# BT_AQ_DOL_R3.net
KiCad netlist of a schematic drawn in EAGLE
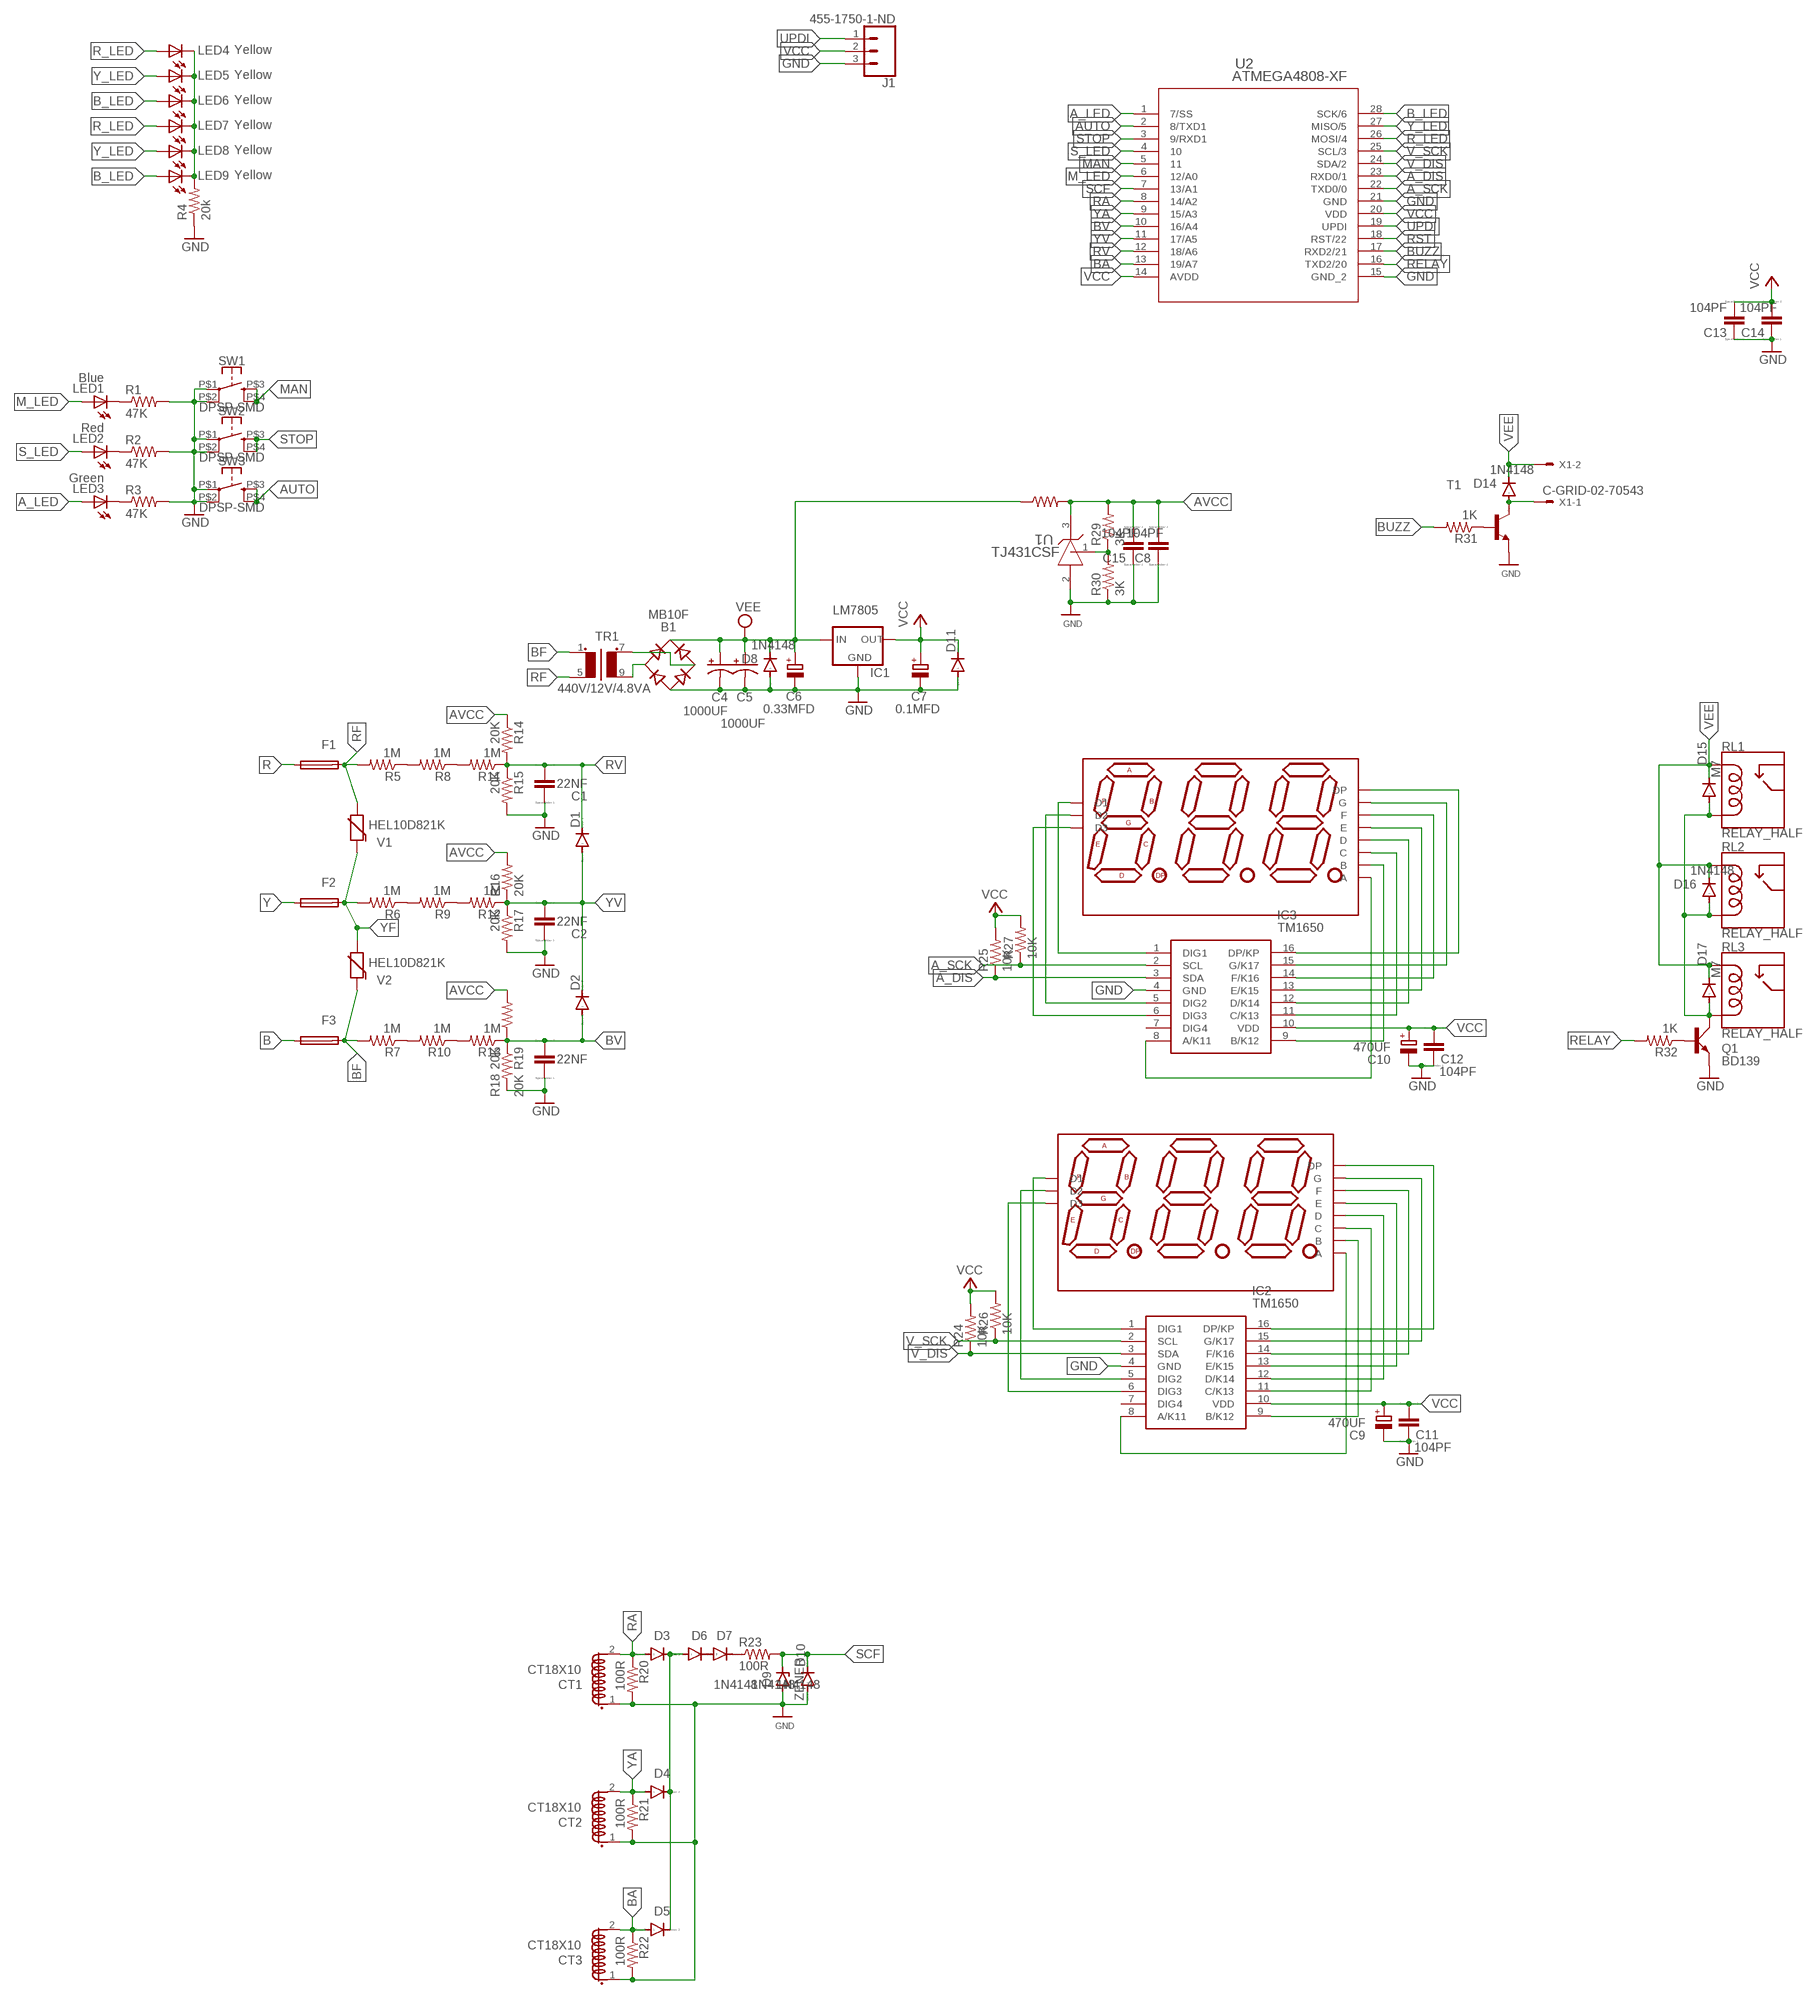
[diagram p0: schematic, sheet 1]

(export (version "E")
  (design (tool "Eeschema 10.0.6"))
  (components
    (comp (ref "B1")
      (value "MB10F")
      (footprint "eagle-import:SOIC-4")
      (libsource (lib "eagle-import") (part "MBS8"))
    )
    (comp (ref "C1")
      (value "22NF")
      (footprint "eagle-import:C1206")
      (libsource (lib "eagle-import") (part "CC1206"))
    )
    (comp (ref "C2")
      (value "22NF")
      (footprint "eagle-import:C1206")
      (libsource (lib "eagle-import") (part "CC1206"))
    )
    (comp (ref "C3")
      (value "22NF")
      (footprint "eagle-import:C1206")
      (libsource (lib "eagle-import") (part "CC1206"))
    )
    (comp (ref "C4")
      (value "1000UF")
      (footprint "eagle-import:E3,5-10")
      (libsource (lib "eagle-import") (part "CPOL-USE3.5-10"))
    )
    (comp (ref "C5")
      (value "1000UF")
      (footprint "eagle-import:E3,5-10")
      (libsource (lib "eagle-import") (part "CPOL-USE3.5-10"))
    )
    (comp (ref "C6")
      (value "0.33MFD")
      (footprint "eagle-import:E2,5-5")
      (libsource (lib "eagle-import") (part "CPOL-EUE2.5-5"))
    )
    (comp (ref "C7")
      (value "0.1MFD")
      (footprint "eagle-import:E2,5-5")
      (libsource (lib "eagle-import") (part "CPOL-EUE2.5-5"))
    )
    (comp (ref "C8")
      (value "104PF")
      (footprint "eagle-import:C1206")
      (libsource (lib "eagle-import") (part "CC1206"))
    )
    (comp (ref "C9")
      (value "470UF")
      (footprint "eagle-import:E3,5-8")
      (libsource (lib "eagle-import") (part "CPOL-EUE3.5-8"))
    )
    (comp (ref "C10")
      (value "470UF")
      (footprint "eagle-import:E3,5-8")
      (libsource (lib "eagle-import") (part "CPOL-EUE3.5-8"))
    )
    (comp (ref "C11")
      (value "104PF")
      (footprint "eagle-import:C1206")
      (libsource (lib "eagle-import") (part "CC1206"))
    )
    (comp (ref "C12")
      (value "104PF")
      (footprint "eagle-import:C1206")
      (libsource (lib "eagle-import") (part "CC1206"))
    )
    (comp (ref "C13")
      (value "104PF")
      (footprint "eagle-import:C1206")
      (libsource (lib "eagle-import") (part "CC1206"))
    )
    (comp (ref "C14")
      (value "104PF")
      (footprint "eagle-import:C1206")
      (libsource (lib "eagle-import") (part "CC1206"))
    )
    (comp (ref "C15")
      (value "104PF")
      (footprint "eagle-import:C1206")
      (libsource (lib "eagle-import") (part "CC1206"))
    )
    (comp (ref "CT1")
      (value "CT18X10")
      (footprint "eagle-import:ZMCT103C")
      (libsource (lib "eagle-import") (part "CT18X10"))
    )
    (comp (ref "CT2")
      (value "CT18X10")
      (footprint "eagle-import:ZMCT103C")
      (libsource (lib "eagle-import") (part "CT18X10"))
    )
    (comp (ref "CT3")
      (value "CT18X10")
      (footprint "eagle-import:ZMCT103C")
      (libsource (lib "eagle-import") (part "CT18X10"))
    )
    (comp (ref "D1")
      (value "DIODE-DO214AA")
      (footprint "eagle-import:DO214AA")
      (libsource (lib "eagle-import") (part "DIODE-DO214AA"))
    )
    (comp (ref "D2")
      (value "DIODE-DO214AA")
      (footprint "eagle-import:DO214AA")
      (libsource (lib "eagle-import") (part "DIODE-DO214AA"))
    )
    (comp (ref "D3")
      (value "1N4148")
      (footprint "eagle-import:MINIMELF")
      (libsource (lib "eagle-import") (part "DIODE-MINIMELF"))
    )
    (comp (ref "D4")
      (value "1N4148")
      (footprint "eagle-import:MINIMELF")
      (libsource (lib "eagle-import") (part "DIODE-MINIMELF"))
    )
    (comp (ref "D5")
      (value "1N4148")
      (footprint "eagle-import:MINIMELF")
      (libsource (lib "eagle-import") (part "DIODE-MINIMELF"))
    )
    (comp (ref "D6")
      (value "1N4148")
      (footprint "eagle-import:MINIMELF")
      (libsource (lib "eagle-import") (part "DIODE-MINIMELF"))
    )
    (comp (ref "D7")
      (value "1N4148")
      (footprint "eagle-import:MINIMELF")
      (libsource (lib "eagle-import") (part "DIODE-MINIMELF"))
    )
    (comp (ref "D8")
      (value "1N4148")
      (footprint "eagle-import:MINIMELF")
      (libsource (lib "eagle-import") (part "DIODE-MINIMELF"))
    )
    (comp (ref "D9")
      (value "ZENER")
      (footprint "eagle-import:DIOMELF3516")
      (libsource (lib "eagle-import") (part "ZENER_DO-213AA(SOD-80)_"))
    )
    (comp (ref "D10")
      (value "DIODE-DO214AA")
      (footprint "eagle-import:DO214AA")
      (libsource (lib "eagle-import") (part "DIODE-DO214AA"))
    )
    (comp (ref "D11")
      (value "DIODE-DO214AA")
      (footprint "eagle-import:DO214AA")
      (libsource (lib "eagle-import") (part "DIODE-DO214AA"))
    )
    (comp (ref "D12")
      (value "SUNR036CC3D")
      (footprint "eagle-import:7S3D036_DIP")
      (libsource (lib "eagle-import") (part "7SEGMENT-3DIGITDIP"))
    )
    (comp (ref "D13")
      (value "SUNR036CC3D")
      (footprint "eagle-import:7S3D036_DIP")
      (libsource (lib "eagle-import") (part "7SEGMENT-3DIGITDIP"))
    )
    (comp (ref "D14")
      (value "1N4148")
      (footprint "eagle-import:MINIMELF")
      (libsource (lib "eagle-import") (part "DIODE-MINIMELF"))
    )
    (comp (ref "D15")
      (value "M7")
      (footprint "eagle-import:DO-214AC")
      (libsource (lib "eagle-import") (part "DIODE-DO-214AC"))
    )
    (comp (ref "D16")
      (value "1N4148")
      (footprint "eagle-import:MINIMELF")
      (libsource (lib "eagle-import") (part "DIODE-MINIMELF"))
    )
    (comp (ref "D17")
      (value "M7")
      (footprint "eagle-import:DO-214AC")
      (libsource (lib "eagle-import") (part "DIODE-DO-214AC"))
    )
    (comp (ref "F1")
      (value "TRF600-150")
      (footprint "eagle-import:TRF600-150")
      (libsource (lib "eagle-import") (part "PPTCPTH"))
    )
    (comp (ref "F2")
      (value "TRF600-150")
      (footprint "eagle-import:TRF600-150")
      (libsource (lib "eagle-import") (part "PPTCPTH"))
    )
    (comp (ref "F3")
      (value "TRF600-150")
      (footprint "eagle-import:TRF600-150")
      (libsource (lib "eagle-import") (part "PPTCPTH"))
    )
    (comp (ref "IC1")
      (value "LM7805")
      (footprint "eagle-import:78XXS")
      (libsource (lib "eagle-import") (part "78XXS"))
    )
    (comp (ref "IC2")
      (value "TM1650")
      (footprint "eagle-import:SOIC127P604X185-16N")
      (fields (field (name "MANUFACTURER_PART_NUMBER") "tm1650"))
      (libsource (lib "eagle-import") (part "TM1650"))
    )
    (comp (ref "IC3")
      (value "TM1650")
      (footprint "eagle-import:SOIC127P604X185-16N")
      (fields (field (name "MANUFACTURER_PART_NUMBER") "tm1650"))
      (libsource (lib "eagle-import") (part "TM1650"))
    )
    (comp (ref "J1")
      (value "455-1750-1-ND")
      (footprint "eagle-import:1X03")
      (libsource (lib "eagle-import") (part "CONN_03"))
    )
    (comp (ref "LED1")
      (value "Blue")
      (footprint "eagle-import:LED3MM")
      (libsource (lib "eagle-import") (part "LED3MM"))
    )
    (comp (ref "LED2")
      (value "Red")
      (footprint "eagle-import:LED3MM")
      (libsource (lib "eagle-import") (part "LED3MM"))
    )
    (comp (ref "LED3")
      (value "Green")
      (footprint "eagle-import:LED3MM")
      (libsource (lib "eagle-import") (part "LED3MM"))
    )
    (comp (ref "LED4")
      (value "Yellow")
      (footprint "eagle-import:LED3MM")
      (libsource (lib "eagle-import") (part "LED3MM"))
    )
    (comp (ref "LED5")
      (value "Yellow")
      (footprint "eagle-import:LED3MM")
      (libsource (lib "eagle-import") (part "LED3MM"))
    )
    (comp (ref "LED6")
      (value "Yellow")
      (footprint "eagle-import:LED3MM")
      (libsource (lib "eagle-import") (part "LED3MM"))
    )
    (comp (ref "LED7")
      (value "Yellow")
      (footprint "eagle-import:LED3MM")
      (libsource (lib "eagle-import") (part "LED3MM"))
    )
    (comp (ref "LED8")
      (value "Yellow")
      (footprint "eagle-import:LED3MM")
      (libsource (lib "eagle-import") (part "LED3MM"))
    )
    (comp (ref "LED9")
      (value "Yellow")
      (footprint "eagle-import:LED3MM")
      (libsource (lib "eagle-import") (part "LED3MM"))
    )
    (comp (ref "Q1")
      (value "BD139")
      (footprint "eagle-import:TO126AV")
      (libsource (lib "eagle-import") (part "BD139"))
    )
    (comp (ref "R1")
      (value "47K")
      (footprint "eagle-import:M1206")
      (libsource (lib "eagle-import") (part "rcl_334_R-US_M1206"))
    )
    (comp (ref "R2")
      (value "47K")
      (footprint "eagle-import:M1206")
      (libsource (lib "eagle-import") (part "rcl_334_R-US_M1206"))
    )
    (comp (ref "R3")
      (value "47K")
      (footprint "eagle-import:M1206")
      (libsource (lib "eagle-import") (part "rcl_334_R-US_M1206"))
    )
    (comp (ref "R4")
      (value "20k")
      (footprint "eagle-import:M1206")
      (libsource (lib "eagle-import") (part "rcl_334_R-US_M1206"))
    )
    (comp (ref "R5")
      (value "1M")
      (footprint "eagle-import:M1206")
      (libsource (lib "eagle-import") (part "rcl_334_R-US_M1206"))
    )
    (comp (ref "R6")
      (value "1M")
      (footprint "eagle-import:M1206")
      (libsource (lib "eagle-import") (part "rcl_334_R-US_M1206"))
    )
    (comp (ref "R7")
      (value "1M")
      (footprint "eagle-import:M1206")
      (libsource (lib "eagle-import") (part "rcl_334_R-US_M1206"))
    )
    (comp (ref "R8")
      (value "1M")
      (footprint "eagle-import:M1206")
      (libsource (lib "eagle-import") (part "rcl_334_R-US_M1206"))
    )
    (comp (ref "R9")
      (value "1M")
      (footprint "eagle-import:M1206")
      (libsource (lib "eagle-import") (part "rcl_334_R-US_M1206"))
    )
    (comp (ref "R10")
      (value "1M")
      (footprint "eagle-import:M1206")
      (libsource (lib "eagle-import") (part "rcl_334_R-US_M1206"))
    )
    (comp (ref "R11")
      (value "1M")
      (footprint "eagle-import:M1206")
      (libsource (lib "eagle-import") (part "rcl_334_R-US_M1206"))
    )
    (comp (ref "R12")
      (value "1M")
      (footprint "eagle-import:M1206")
      (libsource (lib "eagle-import") (part "rcl_334_R-US_M1206"))
    )
    (comp (ref "R13")
      (value "1M")
      (footprint "eagle-import:M1206")
      (libsource (lib "eagle-import") (part "rcl_334_R-US_M1206"))
    )
    (comp (ref "R14")
      (value "20K")
      (footprint "eagle-import:M1206")
      (libsource (lib "eagle-import") (part "rcl_334_R-US_M1206"))
    )
    (comp (ref "R15")
      (value "20K")
      (footprint "eagle-import:M1206")
      (libsource (lib "eagle-import") (part "rcl_334_R-US_M1206"))
    )
    (comp (ref "R16")
      (value "20K")
      (footprint "eagle-import:M1206")
      (libsource (lib "eagle-import") (part "rcl_334_R-US_M1206"))
    )
    (comp (ref "R17")
      (value "20K")
      (footprint "eagle-import:M1206")
      (libsource (lib "eagle-import") (part "rcl_334_R-US_M1206"))
    )
    (comp (ref "R18")
      (value "20K")
      (footprint "eagle-import:M1206")
      (libsource (lib "eagle-import") (part "rcl_334_R-US_M1206"))
    )
    (comp (ref "R19")
      (value "20K")
      (footprint "eagle-import:M1206")
      (libsource (lib "eagle-import") (part "rcl_334_R-US_M1206"))
    )
    (comp (ref "R20")
      (value "100R")
      (footprint "eagle-import:M1206")
      (libsource (lib "eagle-import") (part "R-US_M1206"))
    )
    (comp (ref "R21")
      (value "100R")
      (footprint "eagle-import:M1206")
      (libsource (lib "eagle-import") (part "R-US_M1206"))
    )
    (comp (ref "R22")
      (value "100R")
      (footprint "eagle-import:M1206")
      (libsource (lib "eagle-import") (part "R-US_M1206"))
    )
    (comp (ref "R23")
      (value "100R")
      (footprint "eagle-import:M1206")
      (libsource (lib "eagle-import") (part "R-US_M1206"))
    )
    (comp (ref "R24")
      (value "10K")
      (footprint "eagle-import:M1206")
      (libsource (lib "eagle-import") (part "rcl_334_R-US_M1206"))
    )
    (comp (ref "R25")
      (value "10K")
      (footprint "eagle-import:M1206")
      (libsource (lib "eagle-import") (part "rcl_334_R-US_M1206"))
    )
    (comp (ref "R26")
      (value "10K")
      (footprint "eagle-import:M1206")
      (libsource (lib "eagle-import") (part "rcl_334_R-US_M1206"))
    )
    (comp (ref "R27")
      (value "10K")
      (footprint "eagle-import:M1206")
      (libsource (lib "eagle-import") (part "rcl_334_R-US_M1206"))
    )
    (comp (ref "R28")
      (value "10K")
      (footprint "eagle-import:M1206")
      (libsource (lib "eagle-import") (part "R-US_M1206"))
    )
    (comp (ref "R29")
      (value "3K")
      (footprint "eagle-import:M1206")
      (libsource (lib "eagle-import") (part "R-US_M1206"))
    )
    (comp (ref "R30")
      (value "3K")
      (footprint "eagle-import:M1206")
      (libsource (lib "eagle-import") (part "R-US_M1206"))
    )
    (comp (ref "R31")
      (value "1K")
      (footprint "eagle-import:M1206")
      (libsource (lib "eagle-import") (part "rcl_334_R-US_M1206"))
    )
    (comp (ref "R32")
      (value "1K")
      (footprint "eagle-import:M1206")
      (libsource (lib "eagle-import") (part "rcl_334_R-US_M1206"))
    )
    (comp (ref "RL1")
      (value "RELAY_HALF")
      (footprint "eagle-import:DT90_HALF")
      (libsource (lib "eagle-import") (part "RELAY_HALF"))
    )
    (comp (ref "RL2")
      (value "RELAY_HALF")
      (footprint "eagle-import:DT90_HALF")
      (libsource (lib "eagle-import") (part "RELAY_HALF"))
    )
    (comp (ref "RL3")
      (value "RELAY_HALF")
      (footprint "eagle-import:DT90_HALF")
      (libsource (lib "eagle-import") (part "RELAY_HALF"))
    )
    (comp (ref "SW1")
      (value "DPSP-SMD")
      (footprint "eagle-import:B3F-40XX-ROUND-SMD")
      (libsource (lib "eagle-import") (part "DPSP-SMD"))
    )
    (comp (ref "SW2")
      (value "DPSP-SMD")
      (footprint "eagle-import:B3F-40XX-ROUND-SMD")
      (libsource (lib "eagle-import") (part "DPSP-SMD"))
    )
    (comp (ref "SW3")
      (value "DPSP-SMD")
      (footprint "eagle-import:B3F-40XX-ROUND-SMD")
      (libsource (lib "eagle-import") (part "DPSP-SMD"))
    )
    (comp (ref "T1")
      (value "MMUN2213LT1-NPN-SC59-BEC")
      (footprint "eagle-import:SC59-BEC")
      (libsource (lib "eagle-import") (part "-NPN-SC59-BECMMUN2213LT1"))
    )
    (comp (ref "TR1")
      (value "440V/12V/4.8VA")
      (footprint "eagle-import:440V12V6VA")
      (libsource (lib "eagle-import") (part "TRANSFORMER6VA"))
    )
    (comp (ref "U1")
      (value "TJ431CSF")
      (footprint "eagle-import:SOT-23")
      (fields
        (field (name "MANUFACTURER_PART_NUMBER") "TL431IDBZTG4")
        (field (name "COPYRIGHT") "Copyright (C) 2022 Ultra Librarian. All rights reserved.")
      )
      (libsource (lib "eagle-import") (part "TJ431CSFDBZ0003A_L"))
    )
    (comp (ref "U2")
      (value "ATMEGA4808-XF")
      (footprint "eagle-import:SSOP28_SS_MCH")
      (fields (field (name "COPYRIGHT") "Copyright (C) 2022 Ultra Librarian. All rights reserved."))
      (libsource (lib "eagle-import") (part "ATMEGA4808-XF"))
    )
    (comp (ref "V1")
      (value "HEL10D821K")
      (footprint "eagle-import:10MM")
      (libsource (lib "eagle-import") (part "VARISTOR"))
    )
    (comp (ref "V2")
      (value "HEL10D821K")
      (footprint "eagle-import:10MM")
      (libsource (lib "eagle-import") (part "VARISTOR"))
    )
    (comp (ref "X1")
      (value "C-GRID-02-70543")
      (footprint "eagle-import:70543-02")
      (fields (field (name "MF") "MOLEX"))
      (libsource (lib "eagle-import") (part "C-GRID-02-70543"))
    )
  )
  (nets
    (net (code "1") (name "AUTO") (class "Default")
      (node (ref "SW3") (pin "P$3") (pinfunction "3_P$3") (pintype "passive"))
      (node (ref "SW3") (pin "P$4") (pinfunction "4_P$4") (pintype "passive"))
      (node (ref "U2") (pin "2") (pinfunction "8/TXD1_2") (pintype "bidirectional"))
    )
    (net (code "2") (name "AVCC") (class "Default")
      (node (ref "C15") (pin "2") (pinfunction "2_2") (pintype "passive"))
      (node (ref "C8") (pin "2") (pinfunction "2_2") (pintype "passive"))
      (node (ref "R14") (pin "1") (pinfunction "1_1") (pintype "passive"))
      (node (ref "R16") (pin "2") (pinfunction "2_2") (pintype "passive"))
      (node (ref "R18") (pin "2") (pinfunction "2_2") (pintype "passive"))
      (node (ref "R28") (pin "2") (pinfunction "2_2") (pintype "passive"))
      (node (ref "R29") (pin "2") (pinfunction "2_2") (pintype "passive"))
      (node (ref "U1") (pin "3") (pinfunction "CATHODE_3") (pintype "passive"))
    )
    (net (code "3") (name "A_DIS") (class "Default")
      (node (ref "IC3") (pin "3") (pinfunction "SDA_3") (pintype "input"))
      (node (ref "R25") (pin "1") (pinfunction "1_1") (pintype "passive"))
      (node (ref "U2") (pin "23") (pinfunction "RXD0/1_23") (pintype "bidirectional"))
    )
    (net (code "4") (name "A_LED") (class "Default")
      (node (ref "LED3") (pin "A") (pinfunction "A_A") (pintype "passive"))
      (node (ref "U2") (pin "1") (pinfunction "7/SS_1") (pintype "bidirectional"))
    )
    (net (code "5") (name "A_SCK") (class "Default")
      (node (ref "IC3") (pin "2") (pinfunction "SCL_2") (pintype "input"))
      (node (ref "R27") (pin "1") (pinfunction "1_1") (pintype "passive"))
      (node (ref "U2") (pin "22") (pinfunction "TXD0/0_22") (pintype "bidirectional"))
    )
    (net (code "6") (name "B") (class "Default")
      (node (ref "F3") (pin "1") (pinfunction "1_1") (pintype "passive"))
    )
    (net (code "7") (name "BA") (class "Default")
      (node (ref "CT3") (pin "2") (pinfunction "S1.2_2") (pintype "passive"))
      (node (ref "D5") (pin "A") (pinfunction "A_A") (pintype "passive"))
      (node (ref "R22") (pin "1") (pinfunction "1_1") (pintype "passive"))
      (node (ref "U2") (pin "13") (pinfunction "19/A7_13") (pintype "bidirectional"))
    )
    (net (code "8") (name "BF") (class "Default")
      (node (ref "F3") (pin "2") (pinfunction "2_2") (pintype "passive"))
      (node (ref "R7") (pin "2") (pinfunction "2_2") (pintype "passive"))
      (node (ref "TR1") (pin "1") (pinfunction "P1_1") (pintype "passive"))
      (node (ref "V2") (pin "1") (pinfunction "1_1") (pintype "passive"))
    )
    (net (code "9") (name "BUZZ") (class "Default")
      (node (ref "R31") (pin "2") (pinfunction "2_2") (pintype "passive"))
      (node (ref "U2") (pin "17") (pinfunction "RXD2/21_17") (pintype "bidirectional"))
    )
    (net (code "10") (name "BV") (class "Default")
      (node (ref "C3") (pin "2") (pinfunction "2_2") (pintype "passive"))
      (node (ref "D2") (pin "A") (pinfunction "A_A") (pintype "passive"))
      (node (ref "R13") (pin "1") (pinfunction "1_1") (pintype "passive"))
      (node (ref "R18") (pin "1") (pinfunction "1_1") (pintype "passive"))
      (node (ref "R19") (pin "1") (pinfunction "1_1") (pintype "passive"))
      (node (ref "U2") (pin "10") (pinfunction "16/A4_10") (pintype "bidirectional"))
    )
    (net (code "11") (name "B_LED") (class "Default")
      (node (ref "LED6") (pin "A") (pinfunction "A_A") (pintype "passive"))
      (node (ref "LED9") (pin "A") (pinfunction "A_A") (pintype "passive"))
      (node (ref "U2") (pin "28") (pinfunction "SCK/6_28") (pintype "bidirectional"))
    )
    (net (code "12") (name "GND") (class "Default")
      (node (ref "B1") (pin "-") (pinfunction "-_-") (pintype "passive"))
      (node (ref "C1") (pin "1") (pinfunction "1_1") (pintype "passive"))
      (node (ref "C10") (pin "-") (pinfunction "-_-") (pintype "passive"))
      (node (ref "C11") (pin "1") (pinfunction "1_1") (pintype "passive"))
      (node (ref "C12") (pin "1") (pinfunction "1_1") (pintype "passive"))
      (node (ref "C13") (pin "1") (pinfunction "1_1") (pintype "passive"))
      (node (ref "C14") (pin "1") (pinfunction "1_1") (pintype "passive"))
      (node (ref "C15") (pin "1") (pinfunction "1_1") (pintype "passive"))
      (node (ref "C2") (pin "1") (pinfunction "1_1") (pintype "passive"))
      (node (ref "C3") (pin "1") (pinfunction "1_1") (pintype "passive"))
      (node (ref "C4") (pin "-") (pinfunction "-_-") (pintype "passive"))
      (node (ref "C5") (pin "-") (pinfunction "-_-") (pintype "passive"))
      (node (ref "C6") (pin "-") (pinfunction "-_-") (pintype "passive"))
      (node (ref "C7") (pin "-") (pinfunction "-_-") (pintype "passive"))
      (node (ref "C8") (pin "1") (pinfunction "1_1") (pintype "passive"))
      (node (ref "C9") (pin "-") (pinfunction "-_-") (pintype "passive"))
      (node (ref "CT1") (pin "1") (pinfunction "S1.1_1") (pintype "passive"))
      (node (ref "CT2") (pin "1") (pinfunction "S1.1_1") (pintype "passive"))
      (node (ref "CT3") (pin "1") (pinfunction "S1.1_1") (pintype "passive"))
      (node (ref "D10") (pin "A") (pinfunction "A_A") (pintype "passive"))
      (node (ref "D11") (pin "A") (pinfunction "A_A") (pintype "passive"))
      (node (ref "D8") (pin "A") (pinfunction "A_A") (pintype "passive"))
      (node (ref "D9") (pin "2") (pinfunction "A_2") (pintype "passive"))
      (node (ref "IC1") (pin "GND") (pinfunction "GND_GND") (pintype "input"))
      (node (ref "IC2") (pin "4") (pinfunction "GND_4") (pintype "power_in"))
      (node (ref "IC3") (pin "4") (pinfunction "GND_4") (pintype "power_in"))
      (node (ref "J1") (pin "3") (pinfunction "3_3") (pintype "passive"))
      (node (ref "Q1") (pin "E") (pinfunction "E_E") (pintype "passive"))
      (node (ref "R1") (pin "2") (pinfunction "2_2") (pintype "passive"))
      (node (ref "R15") (pin "2") (pinfunction "2_2") (pintype "passive"))
      (node (ref "R17") (pin "2") (pinfunction "2_2") (pintype "passive"))
      (node (ref "R19") (pin "2") (pinfunction "2_2") (pintype "passive"))
      (node (ref "R2") (pin "2") (pinfunction "2_2") (pintype "passive"))
      (node (ref "R20") (pin "2") (pinfunction "2_2") (pintype "passive"))
      (node (ref "R21") (pin "2") (pinfunction "2_2") (pintype "passive"))
      (node (ref "R22") (pin "2") (pinfunction "2_2") (pintype "passive"))
      (node (ref "R3") (pin "2") (pinfunction "2_2") (pintype "passive"))
      (node (ref "R30") (pin "1") (pinfunction "1_1") (pintype "passive"))
      (node (ref "R4") (pin "1") (pinfunction "1_1") (pintype "passive"))
      (node (ref "SW1") (pin "P$1") (pinfunction "1_P$1") (pintype "passive"))
      (node (ref "SW1") (pin "P$2") (pinfunction "2_P$2") (pintype "passive"))
      (node (ref "SW2") (pin "P$1") (pinfunction "1_P$1") (pintype "passive"))
      (node (ref "SW2") (pin "P$2") (pinfunction "2_P$2") (pintype "passive"))
      (node (ref "SW3") (pin "P$1") (pinfunction "1_P$1") (pintype "passive"))
      (node (ref "SW3") (pin "P$2") (pinfunction "2_P$2") (pintype "passive"))
      (node (ref "T1") (pin "E") (pinfunction "E_E") (pintype "passive"))
      (node (ref "U1") (pin "2") (pinfunction "ANODE_2") (pintype "passive"))
      (node (ref "U2") (pin "15") (pinfunction "GND_2_15") (pintype "passive"))
      (node (ref "U2") (pin "21") (pinfunction "GND_21") (pintype "passive"))
    )
    (net (code "13") (name "MAN") (class "Default")
      (node (ref "SW1") (pin "P$3") (pinfunction "3_P$3") (pintype "passive"))
      (node (ref "SW1") (pin "P$4") (pinfunction "4_P$4") (pintype "passive"))
      (node (ref "U2") (pin "5") (pinfunction "11_5") (pintype "bidirectional"))
    )
    (net (code "14") (name "M_LED") (class "Default")
      (node (ref "LED1") (pin "A") (pinfunction "A_A") (pintype "passive"))
      (node (ref "U2") (pin "6") (pinfunction "12/A0_6") (pintype "bidirectional"))
    )
    (net (code "15") (name "Net-(B1-AC1)") (class "Default")
      (node (ref "B1") (pin "~1") (pinfunction "AC1_~1") (pintype "passive"))
      (node (ref "TR1") (pin "9") (pinfunction "S2_9") (pintype "passive"))
    )
    (net (code "16") (name "Net-(B1-AC2)") (class "Default")
      (node (ref "B1") (pin "~2") (pinfunction "AC2_~2") (pintype "passive"))
      (node (ref "TR1") (pin "7") (pinfunction "S1_7") (pintype "passive"))
    )
    (net (code "17") (name "Net-(D3-PadC)") (class "Default")
      (node (ref "D3") (pin "C") (pinfunction "C_C") (pintype "passive"))
      (node (ref "D4") (pin "C") (pinfunction "C_C") (pintype "passive"))
      (node (ref "D5") (pin "C") (pinfunction "C_C") (pintype "passive"))
      (node (ref "D6") (pin "A") (pinfunction "A_A") (pintype "passive"))
    )
    (net (code "18") (name "Net-(D6-PadC)") (class "Default")
      (node (ref "D6") (pin "C") (pinfunction "C_C") (pintype "passive"))
      (node (ref "D7") (pin "A") (pinfunction "A_A") (pintype "passive"))
    )
    (net (code "19") (name "Net-(D7-PadC)") (class "Default")
      (node (ref "D7") (pin "C") (pinfunction "C_C") (pintype "passive"))
      (node (ref "R23") (pin "1") (pinfunction "1_1") (pintype "passive"))
    )
    (net (code "20") (name "Net-(D12-A)") (class "Default")
      (node (ref "D12") (pin "11") (pinfunction "A_11") (pintype "bidirectional"))
      (node (ref "IC2") (pin "8") (pinfunction "A/K11_8") (pintype "bidirectional"))
    )
    (net (code "21") (name "Net-(D12-B)") (class "Default")
      (node (ref "D12") (pin "7") (pinfunction "B_7") (pintype "bidirectional"))
      (node (ref "IC2") (pin "9") (pinfunction "B/K12_9") (pintype "bidirectional"))
    )
    (net (code "22") (name "Net-(D12-C)") (class "Default")
      (node (ref "D12") (pin "4") (pinfunction "C_4") (pintype "bidirectional"))
      (node (ref "IC2") (pin "11") (pinfunction "C/K13_11") (pintype "bidirectional"))
    )
    (net (code "23") (name "Net-(D12-D)") (class "Default")
      (node (ref "D12") (pin "2") (pinfunction "D_2") (pintype "bidirectional"))
      (node (ref "IC2") (pin "12") (pinfunction "D/K14_12") (pintype "bidirectional"))
    )
    (net (code "24") (name "Net-(D12-D1)") (class "Default")
      (node (ref "D12") (pin "12") (pinfunction "D1_12") (pintype "bidirectional"))
      (node (ref "IC2") (pin "1") (pinfunction "DIG1_1") (pintype "bidirectional"))
    )
    (net (code "25") (name "Net-(D12-D2)") (class "Default")
      (node (ref "D12") (pin "9") (pinfunction "D2_9") (pintype "bidirectional"))
      (node (ref "IC2") (pin "5") (pinfunction "DIG2_5") (pintype "bidirectional"))
    )
    (net (code "26") (name "Net-(D12-D3)") (class "Default")
      (node (ref "D12") (pin "8") (pinfunction "D3_8") (pintype "bidirectional"))
      (node (ref "IC2") (pin "6") (pinfunction "DIG3_6") (pintype "bidirectional"))
    )
    (net (code "27") (name "Net-(D12-DP)") (class "Default")
      (node (ref "D12") (pin "3") (pinfunction "DP_3") (pintype "bidirectional"))
      (node (ref "IC2") (pin "16") (pinfunction "DP/KP_16") (pintype "bidirectional"))
    )
    (net (code "28") (name "Net-(D12-E)") (class "Default")
      (node (ref "D12") (pin "1") (pinfunction "E_1") (pintype "bidirectional"))
      (node (ref "IC2") (pin "13") (pinfunction "E/K15_13") (pintype "bidirectional"))
    )
    (net (code "29") (name "Net-(D12-F)") (class "Default")
      (node (ref "D12") (pin "10") (pinfunction "F_10") (pintype "bidirectional"))
      (node (ref "IC2") (pin "14") (pinfunction "F/K16_14") (pintype "bidirectional"))
    )
    (net (code "30") (name "Net-(D12-G)") (class "Default")
      (node (ref "D12") (pin "5") (pinfunction "G_5") (pintype "bidirectional"))
      (node (ref "IC2") (pin "15") (pinfunction "G/K17_15") (pintype "bidirectional"))
    )
    (net (code "31") (name "Net-(D13-A)") (class "Default")
      (node (ref "D13") (pin "11") (pinfunction "A_11") (pintype "bidirectional"))
      (node (ref "IC3") (pin "8") (pinfunction "A/K11_8") (pintype "bidirectional"))
    )
    (net (code "32") (name "Net-(D13-B)") (class "Default")
      (node (ref "D13") (pin "7") (pinfunction "B_7") (pintype "bidirectional"))
      (node (ref "IC3") (pin "9") (pinfunction "B/K12_9") (pintype "bidirectional"))
    )
    (net (code "33") (name "Net-(D13-C)") (class "Default")
      (node (ref "D13") (pin "4") (pinfunction "C_4") (pintype "bidirectional"))
      (node (ref "IC3") (pin "11") (pinfunction "C/K13_11") (pintype "bidirectional"))
    )
    (net (code "34") (name "Net-(D13-D)") (class "Default")
      (node (ref "D13") (pin "2") (pinfunction "D_2") (pintype "bidirectional"))
      (node (ref "IC3") (pin "12") (pinfunction "D/K14_12") (pintype "bidirectional"))
    )
    (net (code "35") (name "Net-(D13-D1)") (class "Default")
      (node (ref "D13") (pin "12") (pinfunction "D1_12") (pintype "bidirectional"))
      (node (ref "IC3") (pin "1") (pinfunction "DIG1_1") (pintype "bidirectional"))
    )
    (net (code "36") (name "Net-(D13-D2)") (class "Default")
      (node (ref "D13") (pin "9") (pinfunction "D2_9") (pintype "bidirectional"))
      (node (ref "IC3") (pin "5") (pinfunction "DIG2_5") (pintype "bidirectional"))
    )
    (net (code "37") (name "Net-(D13-D3)") (class "Default")
      (node (ref "D13") (pin "8") (pinfunction "D3_8") (pintype "bidirectional"))
      (node (ref "IC3") (pin "6") (pinfunction "DIG3_6") (pintype "bidirectional"))
    )
    (net (code "38") (name "Net-(D13-DP)") (class "Default")
      (node (ref "D13") (pin "3") (pinfunction "DP_3") (pintype "bidirectional"))
      (node (ref "IC3") (pin "16") (pinfunction "DP/KP_16") (pintype "bidirectional"))
    )
    (net (code "39") (name "Net-(D13-E)") (class "Default")
      (node (ref "D13") (pin "1") (pinfunction "E_1") (pintype "bidirectional"))
      (node (ref "IC3") (pin "13") (pinfunction "E/K15_13") (pintype "bidirectional"))
    )
    (net (code "40") (name "Net-(D13-F)") (class "Default")
      (node (ref "D13") (pin "10") (pinfunction "F_10") (pintype "bidirectional"))
      (node (ref "IC3") (pin "14") (pinfunction "F/K16_14") (pintype "bidirectional"))
    )
    (net (code "41") (name "Net-(D13-G)") (class "Default")
      (node (ref "D13") (pin "5") (pinfunction "G_5") (pintype "bidirectional"))
      (node (ref "IC3") (pin "15") (pinfunction "G/K17_15") (pintype "bidirectional"))
    )
    (net (code "42") (name "Net-(LED1-C)") (class "Default")
      (node (ref "LED1") (pin "K") (pinfunction "C_K") (pintype "passive"))
      (node (ref "R1") (pin "1") (pinfunction "1_1") (pintype "passive"))
    )
    (net (code "43") (name "Net-(LED2-C)") (class "Default")
      (node (ref "LED2") (pin "K") (pinfunction "C_K") (pintype "passive"))
      (node (ref "R2") (pin "1") (pinfunction "1_1") (pintype "passive"))
    )
    (net (code "44") (name "Net-(LED3-C)") (class "Default")
      (node (ref "LED3") (pin "K") (pinfunction "C_K") (pintype "passive"))
      (node (ref "R3") (pin "1") (pinfunction "1_1") (pintype "passive"))
    )
    (net (code "45") (name "Net-(LED4-C)") (class "Default")
      (node (ref "LED4") (pin "K") (pinfunction "C_K") (pintype "passive"))
      (node (ref "LED5") (pin "K") (pinfunction "C_K") (pintype "passive"))
      (node (ref "LED6") (pin "K") (pinfunction "C_K") (pintype "passive"))
      (node (ref "LED7") (pin "K") (pinfunction "C_K") (pintype "passive"))
      (node (ref "LED8") (pin "K") (pinfunction "C_K") (pintype "passive"))
      (node (ref "LED9") (pin "K") (pinfunction "C_K") (pintype "passive"))
      (node (ref "R4") (pin "2") (pinfunction "2_2") (pintype "passive"))
    )
    (net (code "46") (name "Net-(Q1-PadB)") (class "Default")
      (node (ref "Q1") (pin "B") (pinfunction "B_B") (pintype "passive"))
      (node (ref "R32") (pin "1") (pinfunction "1_1") (pintype "passive"))
    )
    (net (code "47") (name "Net-(R5-Pad1)") (class "Default")
      (node (ref "R5") (pin "1") (pinfunction "1_1") (pintype "passive"))
      (node (ref "R8") (pin "2") (pinfunction "2_2") (pintype "passive"))
    )
    (net (code "48") (name "Net-(R6-Pad1)") (class "Default")
      (node (ref "R6") (pin "1") (pinfunction "1_1") (pintype "passive"))
      (node (ref "R9") (pin "2") (pinfunction "2_2") (pintype "passive"))
    )
    (net (code "49") (name "Net-(R10-Pad1)") (class "Default")
      (node (ref "R10") (pin "1") (pinfunction "1_1") (pintype "passive"))
      (node (ref "R13") (pin "2") (pinfunction "2_2") (pintype "passive"))
    )
    (net (code "50") (name "Net-(R10-Pad2)") (class "Default")
      (node (ref "R10") (pin "2") (pinfunction "2_2") (pintype "passive"))
      (node (ref "R7") (pin "1") (pinfunction "1_1") (pintype "passive"))
    )
    (net (code "51") (name "Net-(R11-Pad2)") (class "Default")
      (node (ref "R11") (pin "2") (pinfunction "2_2") (pintype "passive"))
      (node (ref "R8") (pin "1") (pinfunction "1_1") (pintype "passive"))
    )
    (net (code "52") (name "Net-(R12-Pad2)") (class "Default")
      (node (ref "R12") (pin "2") (pinfunction "2_2") (pintype "passive"))
      (node (ref "R9") (pin "1") (pinfunction "1_1") (pintype "passive"))
    )
    (net (code "53") (name "Net-(R31-Pad1)") (class "Default")
      (node (ref "R31") (pin "1") (pinfunction "1_1") (pintype "passive"))
      (node (ref "T1") (pin "B") (pinfunction "B_B") (pintype "passive"))
    )
    (net (code "54") (name "Net-(RL1-COIL2)") (class "Default")
      (node (ref "D15") (pin "A") (pinfunction "A_A") (pintype "passive"))
      (node (ref "D16") (pin "A") (pinfunction "A_A") (pintype "passive"))
      (node (ref "D17") (pin "A") (pinfunction "A_A") (pintype "passive"))
      (node (ref "Q1") (pin "C") (pinfunction "C_C") (pintype "passive"))
      (node (ref "RL1") (pin "2") (pinfunction "COIL2_2") (pintype "bidirectional"))
      (node (ref "RL2") (pin "2") (pinfunction "COIL2_2") (pintype "bidirectional"))
      (node (ref "RL3") (pin "2") (pinfunction "COIL2_2") (pintype "bidirectional"))
    )
    (net (code "55") (name "Net-(U1-REF)") (class "Default")
      (node (ref "R29") (pin "1") (pinfunction "1_1") (pintype "passive"))
      (node (ref "R30") (pin "2") (pinfunction "2_2") (pintype "passive"))
      (node (ref "U1") (pin "1") (pinfunction "REF_1") (pintype "input"))
    )
    (net (code "56") (name "Net-(X1A-S)") (class "Default")
      (node (ref "D14") (pin "A") (pinfunction "A_A") (pintype "passive"))
      (node (ref "T1") (pin "C") (pinfunction "C_C") (pintype "passive"))
      (node (ref "X1") (pin "1") (pinfunction "S_1") (pintype "passive"))
    )
    (net (code "57") (name "R") (class "Default")
      (node (ref "F1") (pin "1") (pinfunction "1_1") (pintype "passive"))
    )
    (net (code "58") (name "RA") (class "Default")
      (node (ref "CT1") (pin "2") (pinfunction "S1.2_2") (pintype "passive"))
      (node (ref "D3") (pin "A") (pinfunction "A_A") (pintype "passive"))
      (node (ref "R20") (pin "1") (pinfunction "1_1") (pintype "passive"))
      (node (ref "U2") (pin "8") (pinfunction "14/A2_8") (pintype "bidirectional"))
    )
    (net (code "59") (name "RELAY") (class "Default")
      (node (ref "R32") (pin "2") (pinfunction "2_2") (pintype "passive"))
      (node (ref "U2") (pin "16") (pinfunction "TXD2/20_16") (pintype "bidirectional"))
    )
    (net (code "60") (name "RF") (class "Default")
      (node (ref "F1") (pin "2") (pinfunction "2_2") (pintype "passive"))
      (node (ref "R5") (pin "2") (pinfunction "2_2") (pintype "passive"))
      (node (ref "TR1") (pin "5") (pinfunction "P2_5") (pintype "passive"))
      (node (ref "V1") (pin "2") (pinfunction "2_2") (pintype "passive"))
    )
    (net (code "61") (name "RST") (class "Default")
      (node (ref "U2") (pin "18") (pinfunction "RST/22_18") (pintype "bidirectional"))
    )
    (net (code "62") (name "RV") (class "Default")
      (node (ref "C1") (pin "2") (pinfunction "2_2") (pintype "passive"))
      (node (ref "D1") (pin "C") (pinfunction "C_C") (pintype "passive"))
      (node (ref "R11") (pin "1") (pinfunction "1_1") (pintype "passive"))
      (node (ref "R14") (pin "2") (pinfunction "2_2") (pintype "passive"))
      (node (ref "R15") (pin "1") (pinfunction "1_1") (pintype "passive"))
      (node (ref "U2") (pin "12") (pinfunction "18/A6_12") (pintype "bidirectional"))
    )
    (net (code "63") (name "R_LED") (class "Default")
      (node (ref "LED4") (pin "A") (pinfunction "A_A") (pintype "passive"))
      (node (ref "LED7") (pin "A") (pinfunction "A_A") (pintype "passive"))
      (node (ref "U2") (pin "26") (pinfunction "MOSI/4_26") (pintype "bidirectional"))
    )
    (net (code "64") (name "SCF") (class "Default")
      (node (ref "D10") (pin "C") (pinfunction "C_C") (pintype "passive"))
      (node (ref "D9") (pin "1") (pinfunction "C_1") (pintype "passive"))
      (node (ref "R23") (pin "2") (pinfunction "2_2") (pintype "passive"))
      (node (ref "U2") (pin "7") (pinfunction "13/A1_7") (pintype "bidirectional"))
    )
    (net (code "65") (name "STOP") (class "Default")
      (node (ref "SW2") (pin "P$3") (pinfunction "3_P$3") (pintype "passive"))
      (node (ref "SW2") (pin "P$4") (pinfunction "4_P$4") (pintype "passive"))
      (node (ref "U2") (pin "3") (pinfunction "9/RXD1_3") (pintype "bidirectional"))
    )
    (net (code "66") (name "S_LED") (class "Default")
      (node (ref "LED2") (pin "A") (pinfunction "A_A") (pintype "passive"))
      (node (ref "U2") (pin "4") (pinfunction "10_4") (pintype "bidirectional"))
    )
    (net (code "67") (name "UPDI") (class "Default")
      (node (ref "J1") (pin "1") (pinfunction "1_1") (pintype "passive"))
      (node (ref "U2") (pin "19") (pinfunction "UPDI_19") (pintype "bidirectional"))
    )
    (net (code "68") (name "VCC") (class "Default")
      (node (ref "C10") (pin "+") (pinfunction "+_+") (pintype "passive"))
      (node (ref "C11") (pin "2") (pinfunction "2_2") (pintype "passive"))
      (node (ref "C12") (pin "2") (pinfunction "2_2") (pintype "passive"))
      (node (ref "C13") (pin "2") (pinfunction "2_2") (pintype "passive"))
      (node (ref "C14") (pin "2") (pinfunction "2_2") (pintype "passive"))
      (node (ref "C7") (pin "+") (pinfunction "+_+") (pintype "passive"))
      (node (ref "C9") (pin "+") (pinfunction "+_+") (pintype "passive"))
      (node (ref "D11") (pin "C") (pinfunction "C_C") (pintype "passive"))
      (node (ref "IC1") (pin "OUT") (pinfunction "OUT_OUT") (pintype "passive"))
      (node (ref "IC2") (pin "10") (pinfunction "VDD_10") (pintype "power_in"))
      (node (ref "IC3") (pin "10") (pinfunction "VDD_10") (pintype "power_in"))
      (node (ref "J1") (pin "2") (pinfunction "2_2") (pintype "passive"))
      (node (ref "R24") (pin "2") (pinfunction "2_2") (pintype "passive"))
      (node (ref "R25") (pin "2") (pinfunction "2_2") (pintype "passive"))
      (node (ref "R26") (pin "2") (pinfunction "2_2") (pintype "passive"))
      (node (ref "R27") (pin "2") (pinfunction "2_2") (pintype "passive"))
      (node (ref "U2") (pin "14") (pinfunction "AVDD_14") (pintype "power_in"))
      (node (ref "U2") (pin "20") (pinfunction "VDD_20") (pintype "power_in"))
    )
    (net (code "69") (name "VEE") (class "Default")
      (node (ref "B1") (pin "+") (pinfunction "+_+") (pintype "passive"))
      (node (ref "C4") (pin "+") (pinfunction "+_+") (pintype "passive"))
      (node (ref "C5") (pin "+") (pinfunction "+_+") (pintype "passive"))
      (node (ref "C6") (pin "+") (pinfunction "+_+") (pintype "passive"))
      (node (ref "D14") (pin "C") (pinfunction "C_C") (pintype "passive"))
      (node (ref "D15") (pin "C") (pinfunction "C_C") (pintype "passive"))
      (node (ref "D16") (pin "C") (pinfunction "C_C") (pintype "passive"))
      (node (ref "D17") (pin "C") (pinfunction "C_C") (pintype "passive"))
      (node (ref "D8") (pin "C") (pinfunction "C_C") (pintype "passive"))
      (node (ref "IC1") (pin "IN") (pinfunction "IN_IN") (pintype "input"))
      (node (ref "R28") (pin "1") (pinfunction "1_1") (pintype "passive"))
      (node (ref "RL1") (pin "1") (pinfunction "COIL1_1") (pintype "bidirectional"))
      (node (ref "RL2") (pin "1") (pinfunction "COIL1_1") (pintype "bidirectional"))
      (node (ref "RL3") (pin "1") (pinfunction "COIL1_1") (pintype "bidirectional"))
      (node (ref "X1") (pin "2") (pinfunction "S_2") (pintype "passive"))
    )
    (net (code "70") (name "V_DIS") (class "Default")
      (node (ref "IC2") (pin "3") (pinfunction "SDA_3") (pintype "input"))
      (node (ref "R24") (pin "1") (pinfunction "1_1") (pintype "passive"))
      (node (ref "U2") (pin "24") (pinfunction "SDA/2_24") (pintype "bidirectional"))
    )
    (net (code "71") (name "V_SCK") (class "Default")
      (node (ref "IC2") (pin "2") (pinfunction "SCL_2") (pintype "input"))
      (node (ref "R26") (pin "1") (pinfunction "1_1") (pintype "passive"))
      (node (ref "U2") (pin "25") (pinfunction "SCL/3_25") (pintype "bidirectional"))
    )
    (net (code "72") (name "Y") (class "Default")
      (node (ref "F2") (pin "1") (pinfunction "1_1") (pintype "passive"))
    )
    (net (code "73") (name "YA") (class "Default")
      (node (ref "CT2") (pin "2") (pinfunction "S1.2_2") (pintype "passive"))
      (node (ref "D4") (pin "A") (pinfunction "A_A") (pintype "passive"))
      (node (ref "R21") (pin "1") (pinfunction "1_1") (pintype "passive"))
      (node (ref "U2") (pin "9") (pinfunction "15/A3_9") (pintype "bidirectional"))
    )
    (net (code "74") (name "YF") (class "Default")
      (node (ref "F2") (pin "2") (pinfunction "2_2") (pintype "passive"))
      (node (ref "R6") (pin "2") (pinfunction "2_2") (pintype "passive"))
      (node (ref "V1") (pin "1") (pinfunction "1_1") (pintype "passive"))
      (node (ref "V2") (pin "2") (pinfunction "2_2") (pintype "passive"))
    )
    (net (code "75") (name "YV") (class "Default")
      (node (ref "C2") (pin "2") (pinfunction "2_2") (pintype "passive"))
      (node (ref "D1") (pin "A") (pinfunction "A_A") (pintype "passive"))
      (node (ref "D2") (pin "C") (pinfunction "C_C") (pintype "passive"))
      (node (ref "R12") (pin "1") (pinfunction "1_1") (pintype "passive"))
      (node (ref "R16") (pin "1") (pinfunction "1_1") (pintype "passive"))
      (node (ref "R17") (pin "1") (pinfunction "1_1") (pintype "passive"))
      (node (ref "U2") (pin "11") (pinfunction "17/A5_11") (pintype "bidirectional"))
    )
    (net (code "76") (name "Y_LED") (class "Default")
      (node (ref "LED5") (pin "A") (pinfunction "A_A") (pintype "passive"))
      (node (ref "LED8") (pin "A") (pinfunction "A_A") (pintype "passive"))
      (node (ref "U2") (pin "27") (pinfunction "MISO/5_27") (pintype "bidirectional"))
    )
    (net (code "77") (name "unconnected-(IC2-DIG4-Pad7)") (class "Default")
      (node (ref "IC2") (pin "7") (pinfunction "DIG4_7") (pintype "bidirectional"))
    )
    (net (code "78") (name "unconnected-(IC3-DIG4-Pad7)") (class "Default")
      (node (ref "IC3") (pin "7") (pinfunction "DIG4_7") (pintype "bidirectional"))
    )
  )
)
